# brobot19-MICRO.net
KiCad netlist of a schematic drawn in EAGLE
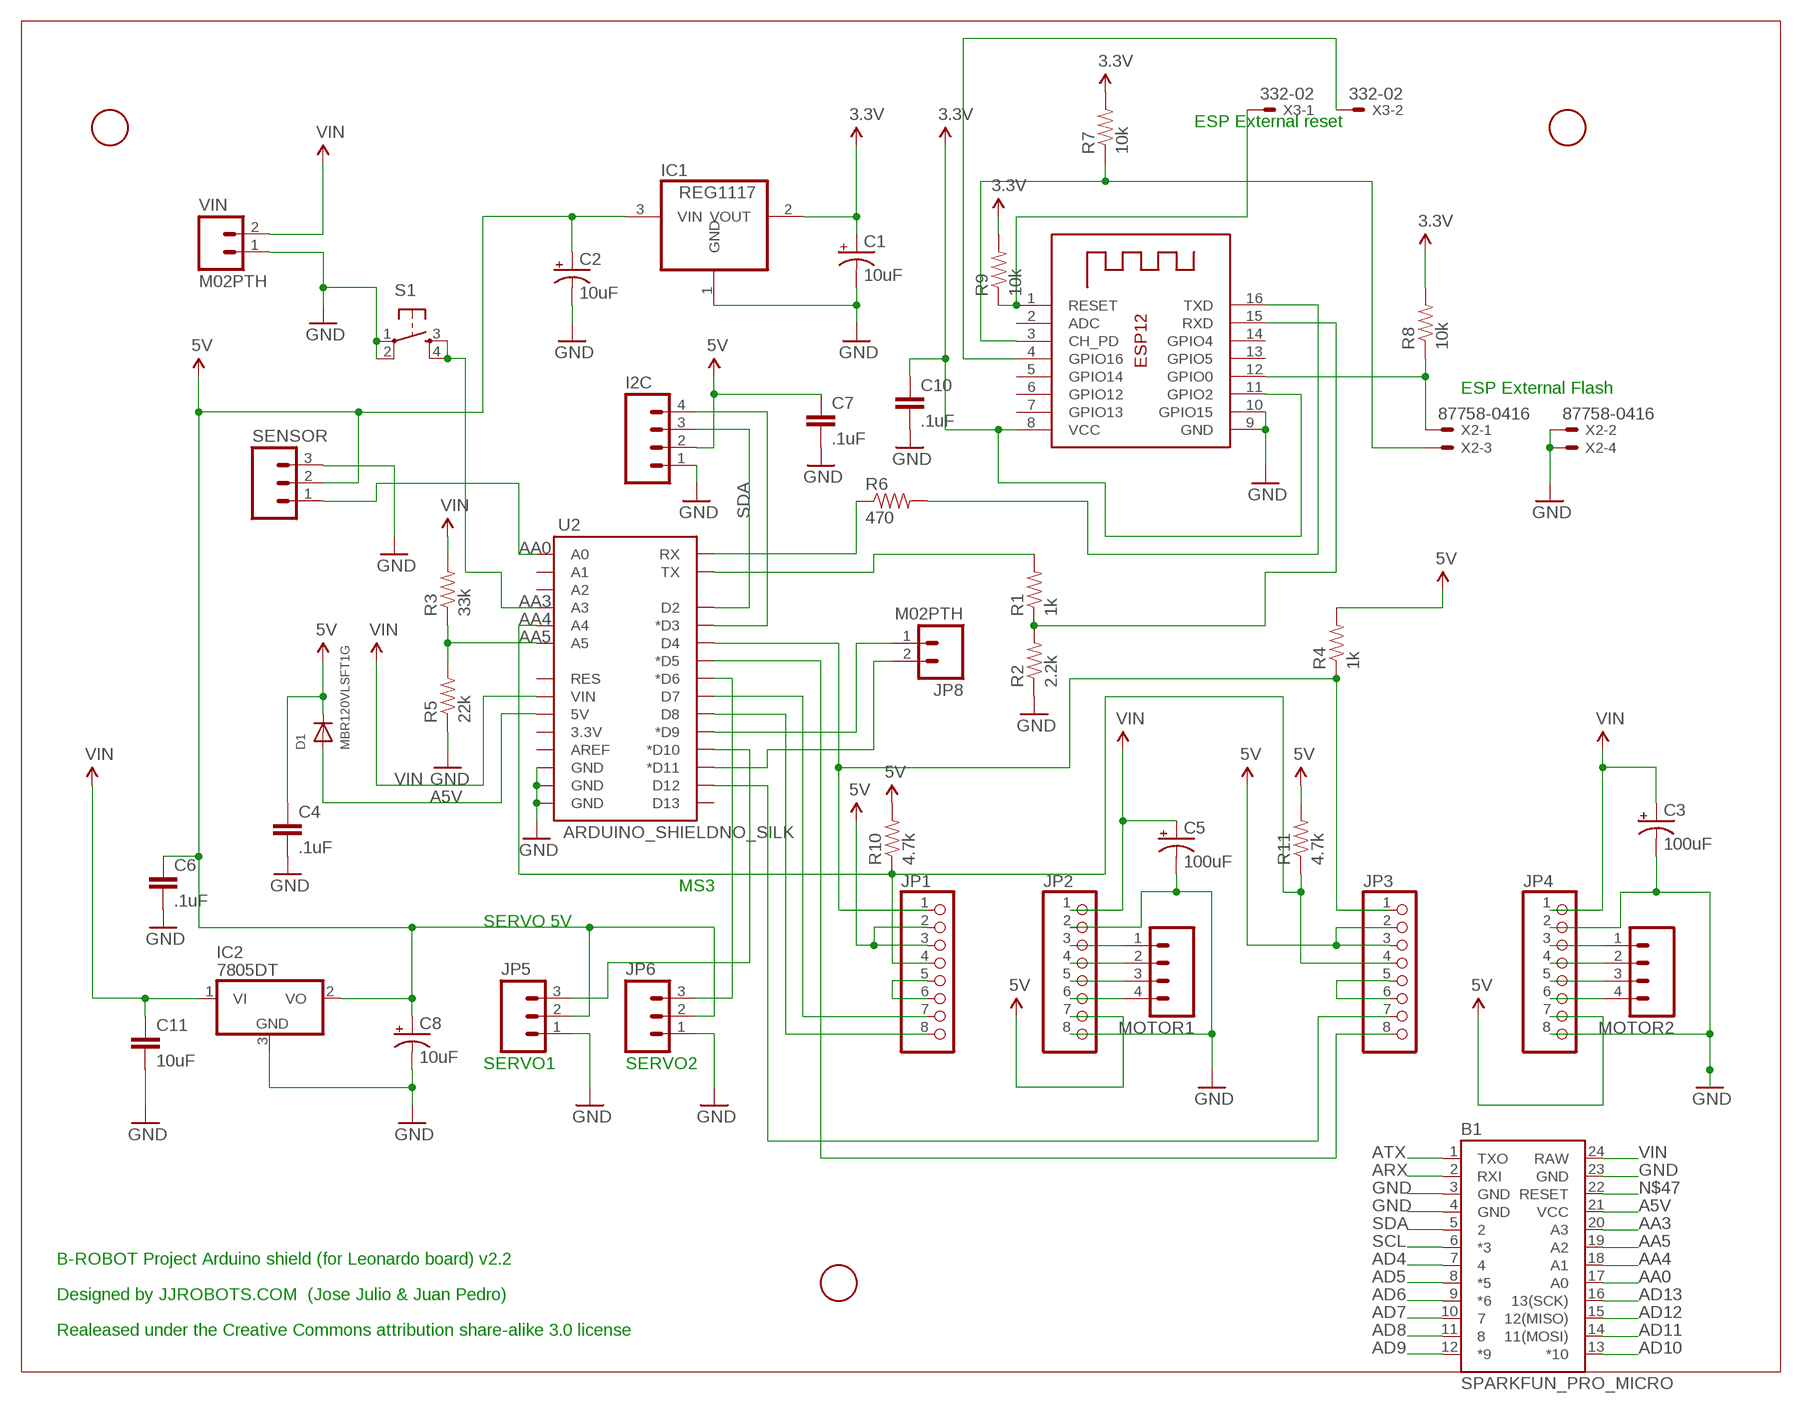
[diagram p0: schematic, sheet 1]

(export (version "E")
  (design (tool "Eeschema 10.0.6"))
  (components
    (comp (ref "B1")
      (value "SPARKFUN_PRO_MICRO")
      (footprint "eagle-import:SPARKFUN_PRO_MICRO")
      (libsource (lib "eagle-import") (part "SPARKFUN_PRO_MICRO"))
    )
    (comp (ref "C1")
      (value "10uF")
      (footprint "eagle-import:EIA3216")
      (libsource (lib "eagle-import") (part "CAP_POL1206"))
    )
    (comp (ref "C2")
      (value "10uF")
      (footprint "eagle-import:EIA3216")
      (libsource (lib "eagle-import") (part "CAP_POL1206"))
    )
    (comp (ref "C3")
      (value "100uF")
      (footprint "eagle-import:PANASONIC_D")
      (libsource (lib "eagle-import") (part "CAP_POLD"))
    )
    (comp (ref "C4")
      (value ".1uF")
      (footprint "eagle-import:0402-CAP")
      (libsource (lib "eagle-import") (part "CAP0402-CAP"))
    )
    (comp (ref "C5")
      (value "100uF")
      (footprint "eagle-import:PANASONIC_D")
      (libsource (lib "eagle-import") (part "CAP_POLD"))
    )
    (comp (ref "C6")
      (value ".1uF")
      (footprint "eagle-import:0402-CAP")
      (libsource (lib "eagle-import") (part "CAP0402-CAP"))
    )
    (comp (ref "C7")
      (value ".1uF")
      (footprint "eagle-import:0402-CAP")
      (libsource (lib "eagle-import") (part "CAP0402-CAP"))
    )
    (comp (ref "C8")
      (value "10uF")
      (footprint "eagle-import:EIA3216")
      (libsource (lib "eagle-import") (part "CAP_POL1206"))
    )
    (comp (ref "C10")
      (value ".1uF")
      (footprint "eagle-import:0402-CAP")
      (libsource (lib "eagle-import") (part "CAP0402-CAP"))
    )
    (comp (ref "C11")
      (value "10uF")
      (footprint "eagle-import:1206")
      (libsource (lib "eagle-import") (part "CAP1206"))
    )
    (comp (ref "D1")
      (value "MBR120VLSFT1G")
      (footprint "eagle-import:SOD-123")
      (libsource (lib "eagle-import") (part "DIODESOD-123"))
    )
    (comp (ref "I2C")
      (value "M04PTH")
      (footprint "eagle-import:1X04")
      (libsource (lib "eagle-import") (part "M04PTH"))
    )
    (comp (ref "IC1")
      (value "REG1117")
      (footprint "eagle-import:SOT223")
      (fields (field (name "MF") "LM1117MPX-3.3/NOPB"))
      (libsource (lib "eagle-import") (part "REG1117"))
    )
    (comp (ref "IC2")
      (value "7805DT")
      (footprint "eagle-import:TO252")
      (libsource (lib "eagle-import") (part "78DT05"))
    )
    (comp (ref "JP1")
      (value "PINHD-1X8")
      (footprint "eagle-import:1X08")
      (libsource (lib "eagle-import") (part "PINHD-1X8"))
    )
    (comp (ref "JP2")
      (value "PINHD-1X8")
      (footprint "eagle-import:1X08")
      (libsource (lib "eagle-import") (part "PINHD-1X8"))
    )
    (comp (ref "JP3")
      (value "PINHD-1X8")
      (footprint "eagle-import:1X08")
      (libsource (lib "eagle-import") (part "PINHD-1X8"))
    )
    (comp (ref "JP4")
      (value "PINHD-1X8")
      (footprint "eagle-import:1X08")
      (libsource (lib "eagle-import") (part "PINHD-1X8"))
    )
    (comp (ref "JP5")
      (value "M03PTH")
      (footprint "eagle-import:1X03")
      (libsource (lib "eagle-import") (part "M03PTH"))
    )
    (comp (ref "JP6")
      (value "M03PTH")
      (footprint "eagle-import:1X03")
      (libsource (lib "eagle-import") (part "M03PTH"))
    )
    (comp (ref "JP8")
      (value "M02PTH")
      (footprint "eagle-import:1X02")
      (libsource (lib "eagle-import") (part "M02PTH"))
    )
    (comp (ref "MOTOR1")
      (value "M04PTH")
      (footprint "eagle-import:1X04")
      (libsource (lib "eagle-import") (part "M04PTH"))
    )
    (comp (ref "MOTOR2")
      (value "M04PTH")
      (footprint "eagle-import:1X04")
      (libsource (lib "eagle-import") (part "M04PTH"))
    )
    (comp (ref "R1")
      (value "1k")
      (footprint "eagle-import:0805")
      (libsource (lib "eagle-import") (part "RESISTOR0805-RES"))
    )
    (comp (ref "R2")
      (value "2.2k")
      (footprint "eagle-import:0805")
      (libsource (lib "eagle-import") (part "RESISTOR0805-RES"))
    )
    (comp (ref "R3")
      (value "33k")
      (footprint "eagle-import:0805")
      (libsource (lib "eagle-import") (part "RESISTOR0805-RES"))
    )
    (comp (ref "R4")
      (value "1k")
      (footprint "eagle-import:0805")
      (libsource (lib "eagle-import") (part "RESISTOR0805-RES"))
    )
    (comp (ref "R5")
      (value "22k")
      (footprint "eagle-import:0805")
      (libsource (lib "eagle-import") (part "RESISTOR0805-RES"))
    )
    (comp (ref "R6")
      (value "470")
      (footprint "eagle-import:0805")
      (libsource (lib "eagle-import") (part "RESISTOR0805-RES"))
    )
    (comp (ref "R7")
      (value "10k")
      (footprint "eagle-import:0805")
      (libsource (lib "eagle-import") (part "RESISTOR0805-RES"))
    )
    (comp (ref "R8")
      (value "10k")
      (footprint "eagle-import:0805")
      (libsource (lib "eagle-import") (part "RESISTOR0805-RES"))
    )
    (comp (ref "R9")
      (value "10k")
      (footprint "eagle-import:0805")
      (libsource (lib "eagle-import") (part "RESISTOR0805-RES"))
    )
    (comp (ref "R10")
      (value "4.7k")
      (footprint "eagle-import:0805")
      (libsource (lib "eagle-import") (part "RESISTOR0805-RES"))
    )
    (comp (ref "R11")
      (value "4.7k")
      (footprint "eagle-import:0805")
      (libsource (lib "eagle-import") (part "RESISTOR0805-RES"))
    )
    (comp (ref "S1")
      (value "TAC_SWITCHSMD")
      (footprint "eagle-import:TACTILE-SWITCH-SMD")
      (libsource (lib "eagle-import") (part "TAC_SWITCHSMD"))
    )
    (comp (ref "SENSOR")
      (value "M03PTH")
      (footprint "eagle-import:1X03")
      (libsource (lib "eagle-import") (part "M03PTH"))
    )
    (comp (ref "U$1")
      (value "FIDUCIAL")
      (footprint "eagle-import:FIDUCIAL_1MM")
      (libsource (lib "eagle-import") (part "FIDUCIAL"))
    )
    (comp (ref "U$2")
      (value "FIDUCIAL")
      (footprint "eagle-import:FIDUCIAL_1MM")
      (libsource (lib "eagle-import") (part "FIDUCIAL"))
    )
    (comp (ref "U$3")
      (value "FIDUCIAL")
      (footprint "eagle-import:FIDUCIAL_1MM")
      (libsource (lib "eagle-import") (part "FIDUCIAL"))
    )
    (comp (ref "U2")
      (value "ARDUINO_SHIELDNO_SILK")
      (footprint "eagle-import:DUEMILANOVE_VIAS")
      (libsource (lib "eagle-import") (part "ARDUINO_SHIELDNO_SILK"))
    )
    (comp (ref "VIN")
      (value "M02PTH")
      (footprint "eagle-import:1X02")
      (libsource (lib "eagle-import") (part "M02PTH"))
    )
    (comp (ref "X1")
      (value "ESP-12")
      (footprint "eagle-import:ESP-12")
      (libsource (lib "eagle-import") (part "ESP-12"))
    )
    (comp (ref "X2")
      (value "87758-0416")
      (footprint "eagle-import:87758-0416")
      (fields (field (name "MF") "FARNELL"))
      (libsource (lib "eagle-import") (part "87758-0416"))
    )
    (comp (ref "X3")
      (value "332-02")
      (footprint "eagle-import:332-02")
      (libsource (lib "eagle-import") (part "332-02"))
    )
  )
  (nets
    (net (code "1") (name "/A5V") (class "Default")
      (node (ref "B1") (pin "21") (pinfunction "VCC_21") (pintype "power_in"))
      (node (ref "D1") (pin "A") (pinfunction "A_A") (pintype "passive"))
      (node (ref "U2") (pin "5V") (pinfunction "5V_5V") (pintype "bidirectional"))
    )
    (net (code "2") (name "/AA0") (class "Default")
      (node (ref "B1") (pin "17") (pinfunction "A0_17") (pintype "bidirectional"))
      (node (ref "SENSOR") (pin "1") (pinfunction "1_1") (pintype "passive"))
      (node (ref "U2") (pin "A0") (pinfunction "A0_A0") (pintype "bidirectional"))
    )
    (net (code "3") (name "/AA3") (class "Default")
      (node (ref "B1") (pin "20") (pinfunction "A3_20") (pintype "bidirectional"))
      (node (ref "S1") (pin "3") (pinfunction "3_3") (pintype "passive"))
      (node (ref "S1") (pin "4") (pinfunction "4_4") (pintype "passive"))
      (node (ref "U2") (pin "A3") (pinfunction "A3_A3") (pintype "bidirectional"))
    )
    (net (code "4") (name "/AA4") (class "Default")
      (node (ref "B1") (pin "18") (pinfunction "A1_18") (pintype "bidirectional"))
      (node (ref "JP1") (pin "4") (pinfunction "4_4") (pintype "passive"))
      (node (ref "JP3") (pin "4") (pinfunction "4_4") (pintype "passive"))
      (node (ref "R10") (pin "1") (pinfunction "1_1") (pintype "passive"))
      (node (ref "R11") (pin "1") (pinfunction "1_1") (pintype "passive"))
      (node (ref "U2") (pin "A4") (pinfunction "A4_A4") (pintype "bidirectional"))
    )
    (net (code "5") (name "/AA5") (class "Default")
      (node (ref "B1") (pin "19") (pinfunction "A2_19") (pintype "bidirectional"))
      (node (ref "R3") (pin "1") (pinfunction "1_1") (pintype "passive"))
      (node (ref "R5") (pin "2") (pinfunction "2_2") (pintype "passive"))
      (node (ref "U2") (pin "A5") (pinfunction "A5_A5") (pintype "bidirectional"))
    )
    (net (code "6") (name "/AD4") (class "Default")
      (node (ref "B1") (pin "7") (pinfunction "4_7") (pintype "bidirectional"))
      (node (ref "JP1") (pin "1") (pinfunction "1_1") (pintype "passive"))
      (node (ref "JP3") (pin "1") (pinfunction "1_1") (pintype "passive"))
      (node (ref "R4") (pin "1") (pinfunction "1_1") (pintype "passive"))
      (node (ref "U2") (pin "D4") (pinfunction "D4_D4") (pintype "bidirectional"))
    )
    (net (code "7") (name "/AD5") (class "Default")
      (node (ref "B1") (pin "8") (pinfunction "*5_8") (pintype "bidirectional"))
      (node (ref "JP3") (pin "8") (pinfunction "8_8") (pintype "passive"))
      (node (ref "U2") (pin "D5") (pinfunction "*D5_D5") (pintype "bidirectional"))
    )
    (net (code "8") (name "/AD6") (class "Default")
      (node (ref "B1") (pin "9") (pinfunction "*6_9") (pintype "bidirectional"))
      (node (ref "JP6") (pin "3") (pinfunction "3_3") (pintype "passive"))
      (node (ref "U2") (pin "D6") (pinfunction "*D6_D6") (pintype "bidirectional"))
    )
    (net (code "9") (name "/AD7") (class "Default")
      (node (ref "B1") (pin "10") (pinfunction "7_10") (pintype "bidirectional"))
      (node (ref "JP1") (pin "7") (pinfunction "7_7") (pintype "passive"))
      (node (ref "U2") (pin "D7") (pinfunction "D7_D7") (pintype "bidirectional"))
    )
    (net (code "10") (name "/AD8") (class "Default")
      (node (ref "B1") (pin "11") (pinfunction "8_11") (pintype "bidirectional"))
      (node (ref "JP1") (pin "8") (pinfunction "8_8") (pintype "passive"))
      (node (ref "U2") (pin "D8") (pinfunction "D8_D8") (pintype "bidirectional"))
    )
    (net (code "11") (name "/AD9") (class "Default")
      (node (ref "B1") (pin "12") (pinfunction "*9_12") (pintype "bidirectional"))
      (node (ref "JP8") (pin "1") (pinfunction "1_1") (pintype "passive"))
      (node (ref "U2") (pin "D9") (pinfunction "*D9_D9") (pintype "bidirectional"))
    )
    (net (code "12") (name "/AD10") (class "Default")
      (node (ref "B1") (pin "13") (pinfunction "*10_13") (pintype "bidirectional"))
      (node (ref "JP5") (pin "3") (pinfunction "3_3") (pintype "passive"))
      (node (ref "U2") (pin "D10") (pinfunction "*D10_D10") (pintype "bidirectional"))
    )
    (net (code "13") (name "/AD11") (class "Default")
      (node (ref "B1") (pin "14") (pinfunction "11(MOSI)_14") (pintype "bidirectional"))
      (node (ref "JP8") (pin "2") (pinfunction "2_2") (pintype "passive"))
      (node (ref "U2") (pin "D11") (pinfunction "*D11_D11") (pintype "bidirectional"))
    )
    (net (code "14") (name "/AD12") (class "Default")
      (node (ref "B1") (pin "15") (pinfunction "12(MISO)_15") (pintype "bidirectional"))
      (node (ref "JP3") (pin "7") (pinfunction "7_7") (pintype "passive"))
      (node (ref "U2") (pin "D12") (pinfunction "D12_D12") (pintype "bidirectional"))
    )
    (net (code "15") (name "/AD13") (class "Default")
      (node (ref "B1") (pin "16") (pinfunction "13(SCK)_16") (pintype "bidirectional"))
    )
    (net (code "16") (name "/ARX") (class "Default")
      (node (ref "B1") (pin "2") (pinfunction "RXI_2") (pintype "bidirectional"))
      (node (ref "R6") (pin "1") (pinfunction "1_1") (pintype "passive"))
      (node (ref "U2") (pin "RX") (pinfunction "RX_RX") (pintype "bidirectional"))
    )
    (net (code "17") (name "/ATX") (class "Default")
      (node (ref "B1") (pin "1") (pinfunction "TXO_1") (pintype "bidirectional"))
      (node (ref "R1") (pin "2") (pinfunction "2_2") (pintype "passive"))
      (node (ref "U2") (pin "TX") (pinfunction "TX_TX") (pintype "bidirectional"))
    )
    (net (code "18") (name "/N$47") (class "Default")
      (node (ref "B1") (pin "22") (pinfunction "RESET_22") (pintype "bidirectional"))
    )
    (net (code "19") (name "/SCL") (class "Default")
      (node (ref "B1") (pin "6") (pinfunction "*3_6") (pintype "bidirectional"))
      (node (ref "I2C") (pin "4") (pinfunction "4_4") (pintype "passive"))
      (node (ref "U2") (pin "D3") (pinfunction "*D3_D3") (pintype "bidirectional"))
    )
    (net (code "20") (name "/SDA") (class "Default")
      (node (ref "B1") (pin "5") (pinfunction "2_5") (pintype "bidirectional"))
      (node (ref "I2C") (pin "3") (pinfunction "3_3") (pintype "passive"))
      (node (ref "U2") (pin "D2") (pinfunction "D2_D2") (pintype "bidirectional"))
    )
    (net (code "21") (name "3.3V") (class "Default")
      (node (ref "C1") (pin "A") (pinfunction "+_A") (pintype "passive"))
      (node (ref "C10") (pin "1") (pinfunction "1_1") (pintype "passive"))
      (node (ref "IC1") (pin "2") (pinfunction "VOUT_2") (pintype "output"))
      (node (ref "R7") (pin "2") (pinfunction "2_2") (pintype "passive"))
      (node (ref "R8") (pin "2") (pinfunction "2_2") (pintype "passive"))
      (node (ref "R9") (pin "2") (pinfunction "2_2") (pintype "passive"))
      (node (ref "X1") (pin "11") (pinfunction "GPIO2_11") (pintype "bidirectional"))
      (node (ref "X1") (pin "8") (pinfunction "VCC_8") (pintype "power_in"))
    )
    (net (code "22") (name "5V") (class "Default")
      (node (ref "C2") (pin "A") (pinfunction "+_A") (pintype "passive"))
      (node (ref "C4") (pin "1") (pinfunction "1_1") (pintype "passive"))
      (node (ref "C6") (pin "1") (pinfunction "1_1") (pintype "passive"))
      (node (ref "C7") (pin "1") (pinfunction "1_1") (pintype "passive"))
      (node (ref "C8") (pin "A") (pinfunction "+_A") (pintype "passive"))
      (node (ref "D1") (pin "C") (pinfunction "C_C") (pintype "passive"))
      (node (ref "I2C") (pin "2") (pinfunction "2_2") (pintype "passive"))
      (node (ref "IC1") (pin "3") (pinfunction "VIN_3") (pintype "input"))
      (node (ref "IC2") (pin "2") (pinfunction "VO_2") (pintype "passive"))
      (node (ref "JP1") (pin "2") (pinfunction "2_2") (pintype "passive"))
      (node (ref "JP1") (pin "3") (pinfunction "3_3") (pintype "passive"))
      (node (ref "JP2") (pin "7") (pinfunction "7_7") (pintype "passive"))
      (node (ref "JP3") (pin "2") (pinfunction "2_2") (pintype "passive"))
      (node (ref "JP3") (pin "3") (pinfunction "3_3") (pintype "passive"))
      (node (ref "JP4") (pin "7") (pinfunction "7_7") (pintype "passive"))
      (node (ref "JP5") (pin "2") (pinfunction "2_2") (pintype "passive"))
      (node (ref "JP6") (pin "2") (pinfunction "2_2") (pintype "passive"))
      (node (ref "R10") (pin "2") (pinfunction "2_2") (pintype "passive"))
      (node (ref "R11") (pin "2") (pinfunction "2_2") (pintype "passive"))
      (node (ref "R4") (pin "2") (pinfunction "2_2") (pintype "passive"))
      (node (ref "SENSOR") (pin "2") (pinfunction "2_2") (pintype "passive"))
    )
    (net (code "23") (name "GND") (class "Default")
      (node (ref "B1") (pin "23") (pinfunction "GND_23") (pintype "power_in"))
      (node (ref "B1") (pin "3") (pinfunction "GND_3") (pintype "power_in"))
      (node (ref "B1") (pin "4") (pinfunction "GND_4") (pintype "power_in"))
      (node (ref "C1") (pin "C") (pinfunction "-_C") (pintype "passive"))
      (node (ref "C10") (pin "2") (pinfunction "2_2") (pintype "passive"))
      (node (ref "C11") (pin "2") (pinfunction "2_2") (pintype "passive"))
      (node (ref "C2") (pin "C") (pinfunction "-_C") (pintype "passive"))
      (node (ref "C3") (pin "-") (pinfunction "-_-") (pintype "passive"))
      (node (ref "C4") (pin "2") (pinfunction "2_2") (pintype "passive"))
      (node (ref "C5") (pin "-") (pinfunction "-_-") (pintype "passive"))
      (node (ref "C6") (pin "2") (pinfunction "2_2") (pintype "passive"))
      (node (ref "C7") (pin "2") (pinfunction "2_2") (pintype "passive"))
      (node (ref "C8") (pin "C") (pinfunction "-_C") (pintype "passive"))
      (node (ref "I2C") (pin "1") (pinfunction "1_1") (pintype "passive"))
      (node (ref "IC1") (pin "1") (pinfunction "GND_1") (pintype "power_in"))
      (node (ref "IC2") (pin "3") (pinfunction "GND_3") (pintype "passive"))
      (node (ref "JP2") (pin "2") (pinfunction "2_2") (pintype "passive"))
      (node (ref "JP2") (pin "8") (pinfunction "8_8") (pintype "passive"))
      (node (ref "JP4") (pin "2") (pinfunction "2_2") (pintype "passive"))
      (node (ref "JP4") (pin "8") (pinfunction "8_8") (pintype "passive"))
      (node (ref "JP5") (pin "1") (pinfunction "1_1") (pintype "passive"))
      (node (ref "JP6") (pin "1") (pinfunction "1_1") (pintype "passive"))
      (node (ref "R2") (pin "1") (pinfunction "1_1") (pintype "passive"))
      (node (ref "R5") (pin "1") (pinfunction "1_1") (pintype "passive"))
      (node (ref "S1") (pin "1") (pinfunction "1_1") (pintype "passive"))
      (node (ref "S1") (pin "2") (pinfunction "2_2") (pintype "passive"))
      (node (ref "SENSOR") (pin "3") (pinfunction "3_3") (pintype "passive"))
      (node (ref "U2") (pin "GND@0") (pinfunction "GND_GND@0") (pintype "bidirectional"))
      (node (ref "U2") (pin "GND@1") (pinfunction "GND_GND@1") (pintype "bidirectional"))
      (node (ref "U2") (pin "GND@2") (pinfunction "GND_GND@2") (pintype "bidirectional"))
      (node (ref "VIN") (pin "1") (pinfunction "1_1") (pintype "passive"))
      (node (ref "X1") (pin "10") (pinfunction "GPIO15_10") (pintype "bidirectional"))
      (node (ref "X1") (pin "9") (pinfunction "GND_9") (pintype "power_in"))
      (node (ref "X2") (pin "2") (pinfunction "S_2") (pintype "passive"))
      (node (ref "X2") (pin "4") (pinfunction "S_4") (pintype "passive"))
    )
    (net (code "24") (name "Net-(JP1-Pad5)") (class "Default")
      (node (ref "JP1") (pin "5") (pinfunction "5_5") (pintype "passive"))
      (node (ref "JP1") (pin "6") (pinfunction "6_6") (pintype "passive"))
    )
    (net (code "25") (name "Net-(JP2-Pad3)") (class "Default")
      (node (ref "JP2") (pin "3") (pinfunction "3_3") (pintype "passive"))
      (node (ref "MOTOR1") (pin "1") (pinfunction "1_1") (pintype "passive"))
    )
    (net (code "26") (name "Net-(JP2-Pad4)") (class "Default")
      (node (ref "JP2") (pin "4") (pinfunction "4_4") (pintype "passive"))
      (node (ref "MOTOR1") (pin "2") (pinfunction "2_2") (pintype "passive"))
    )
    (net (code "27") (name "Net-(JP2-Pad5)") (class "Default")
      (node (ref "JP2") (pin "5") (pinfunction "5_5") (pintype "passive"))
      (node (ref "MOTOR1") (pin "3") (pinfunction "3_3") (pintype "passive"))
    )
    (net (code "28") (name "Net-(JP2-Pad6)") (class "Default")
      (node (ref "JP2") (pin "6") (pinfunction "6_6") (pintype "passive"))
      (node (ref "MOTOR1") (pin "4") (pinfunction "4_4") (pintype "passive"))
    )
    (net (code "29") (name "Net-(JP3-Pad5)") (class "Default")
      (node (ref "JP3") (pin "5") (pinfunction "5_5") (pintype "passive"))
      (node (ref "JP3") (pin "6") (pinfunction "6_6") (pintype "passive"))
    )
    (net (code "30") (name "Net-(JP4-Pad3)") (class "Default")
      (node (ref "JP4") (pin "3") (pinfunction "3_3") (pintype "passive"))
      (node (ref "MOTOR2") (pin "1") (pinfunction "1_1") (pintype "passive"))
    )
    (net (code "31") (name "Net-(JP4-Pad4)") (class "Default")
      (node (ref "JP4") (pin "4") (pinfunction "4_4") (pintype "passive"))
      (node (ref "MOTOR2") (pin "2") (pinfunction "2_2") (pintype "passive"))
    )
    (net (code "32") (name "Net-(JP4-Pad5)") (class "Default")
      (node (ref "JP4") (pin "5") (pinfunction "5_5") (pintype "passive"))
      (node (ref "MOTOR2") (pin "3") (pinfunction "3_3") (pintype "passive"))
    )
    (net (code "33") (name "Net-(JP4-Pad6)") (class "Default")
      (node (ref "JP4") (pin "6") (pinfunction "6_6") (pintype "passive"))
      (node (ref "MOTOR2") (pin "4") (pinfunction "4_4") (pintype "passive"))
    )
    (net (code "34") (name "Net-(X1-CH_PD)") (class "Default")
      (node (ref "R7") (pin "1") (pinfunction "1_1") (pintype "passive"))
      (node (ref "X1") (pin "3") (pinfunction "CH_PD_3") (pintype "input"))
      (node (ref "X2") (pin "3") (pinfunction "S_3") (pintype "passive"))
    )
    (net (code "35") (name "Net-(X1-GPIO0)") (class "Default")
      (node (ref "R8") (pin "1") (pinfunction "1_1") (pintype "passive"))
      (node (ref "X1") (pin "12") (pinfunction "GPIO0_12") (pintype "bidirectional"))
      (node (ref "X2") (pin "1") (pinfunction "S_1") (pintype "passive"))
    )
    (net (code "36") (name "Net-(X1-GPIO16)") (class "Default")
      (node (ref "X1") (pin "4") (pinfunction "GPIO16_4") (pintype "bidirectional"))
      (node (ref "X3") (pin "2") (pinfunction "S_2") (pintype "passive"))
    )
    (net (code "37") (name "Net-(X1-RESET)") (class "Default")
      (node (ref "R9") (pin "1") (pinfunction "1_1") (pintype "passive"))
      (node (ref "X1") (pin "1") (pinfunction "RESET_1") (pintype "input"))
      (node (ref "X3") (pin "1") (pinfunction "S_1") (pintype "passive"))
    )
    (net (code "38") (name "Net-(X1-RXD)") (class "Default")
      (node (ref "R1") (pin "1") (pinfunction "1_1") (pintype "passive"))
      (node (ref "R2") (pin "2") (pinfunction "2_2") (pintype "passive"))
      (node (ref "X1") (pin "15") (pinfunction "RXD_15") (pintype "input"))
    )
    (net (code "39") (name "Net-(X1-TXD)") (class "Default")
      (node (ref "R6") (pin "2") (pinfunction "2_2") (pintype "passive"))
      (node (ref "X1") (pin "16") (pinfunction "TXD_16") (pintype "output"))
    )
    (net (code "40") (name "VIN") (class "Default")
      (node (ref "B1") (pin "24") (pinfunction "RAW_24") (pintype "power_in"))
      (node (ref "C11") (pin "1") (pinfunction "1_1") (pintype "passive"))
      (node (ref "C3") (pin "+") (pinfunction "+_+") (pintype "passive"))
      (node (ref "C5") (pin "+") (pinfunction "+_+") (pintype "passive"))
      (node (ref "IC2") (pin "1") (pinfunction "VI_1") (pintype "input"))
      (node (ref "JP2") (pin "1") (pinfunction "1_1") (pintype "passive"))
      (node (ref "JP4") (pin "1") (pinfunction "1_1") (pintype "passive"))
      (node (ref "R3") (pin "2") (pinfunction "2_2") (pintype "passive"))
      (node (ref "U2") (pin "VIN") (pinfunction "VIN_VIN") (pintype "bidirectional"))
      (node (ref "VIN") (pin "2") (pinfunction "2_2") (pintype "passive"))
    )
    (net (code "41") (name "unconnected-(U2-Pad3.3V)") (class "Default")
      (node (ref "U2") (pin "3.3V") (pinfunction "3.3V_3.3V") (pintype "bidirectional"))
    )
    (net (code "42") (name "unconnected-(U2-PadA1)") (class "Default")
      (node (ref "U2") (pin "A1") (pinfunction "A1_A1") (pintype "bidirectional"))
    )
    (net (code "43") (name "unconnected-(U2-PadA2)") (class "Default")
      (node (ref "U2") (pin "A2") (pinfunction "A2_A2") (pintype "bidirectional"))
    )
    (net (code "44") (name "unconnected-(U2-PadAREF)") (class "Default")
      (node (ref "U2") (pin "AREF") (pinfunction "AREF_AREF") (pintype "bidirectional"))
    )
    (net (code "45") (name "unconnected-(U2-PadD13)") (class "Default")
      (node (ref "U2") (pin "D13") (pinfunction "D13_D13") (pintype "bidirectional"))
    )
    (net (code "46") (name "unconnected-(U2-PadRES)") (class "Default")
      (node (ref "U2") (pin "RES") (pinfunction "RES_RES") (pintype "bidirectional"))
    )
    (net (code "47") (name "unconnected-(X1-ADC-Pad2)") (class "Default")
      (node (ref "X1") (pin "2") (pinfunction "ADC_2") (pintype "passive"))
    )
    (net (code "48") (name "unconnected-(X1-GPIO4-Pad14)") (class "Default")
      (node (ref "X1") (pin "14") (pinfunction "GPIO4_14") (pintype "bidirectional"))
    )
    (net (code "49") (name "unconnected-(X1-GPIO5-Pad13)") (class "Default")
      (node (ref "X1") (pin "13") (pinfunction "GPIO5_13") (pintype "bidirectional"))
    )
    (net (code "50") (name "unconnected-(X1-GPIO12-Pad6)") (class "Default")
      (node (ref "X1") (pin "6") (pinfunction "GPIO12_6") (pintype "bidirectional"))
    )
    (net (code "51") (name "unconnected-(X1-GPIO13-Pad7)") (class "Default")
      (node (ref "X1") (pin "7") (pinfunction "GPIO13_7") (pintype "bidirectional"))
    )
    (net (code "52") (name "unconnected-(X1-GPIO14-Pad5)") (class "Default")
      (node (ref "X1") (pin "5") (pinfunction "GPIO14_5") (pintype "bidirectional"))
    )
  )
)
